# main.net
KiCad netlist of a schematic drawn in Altium Designer
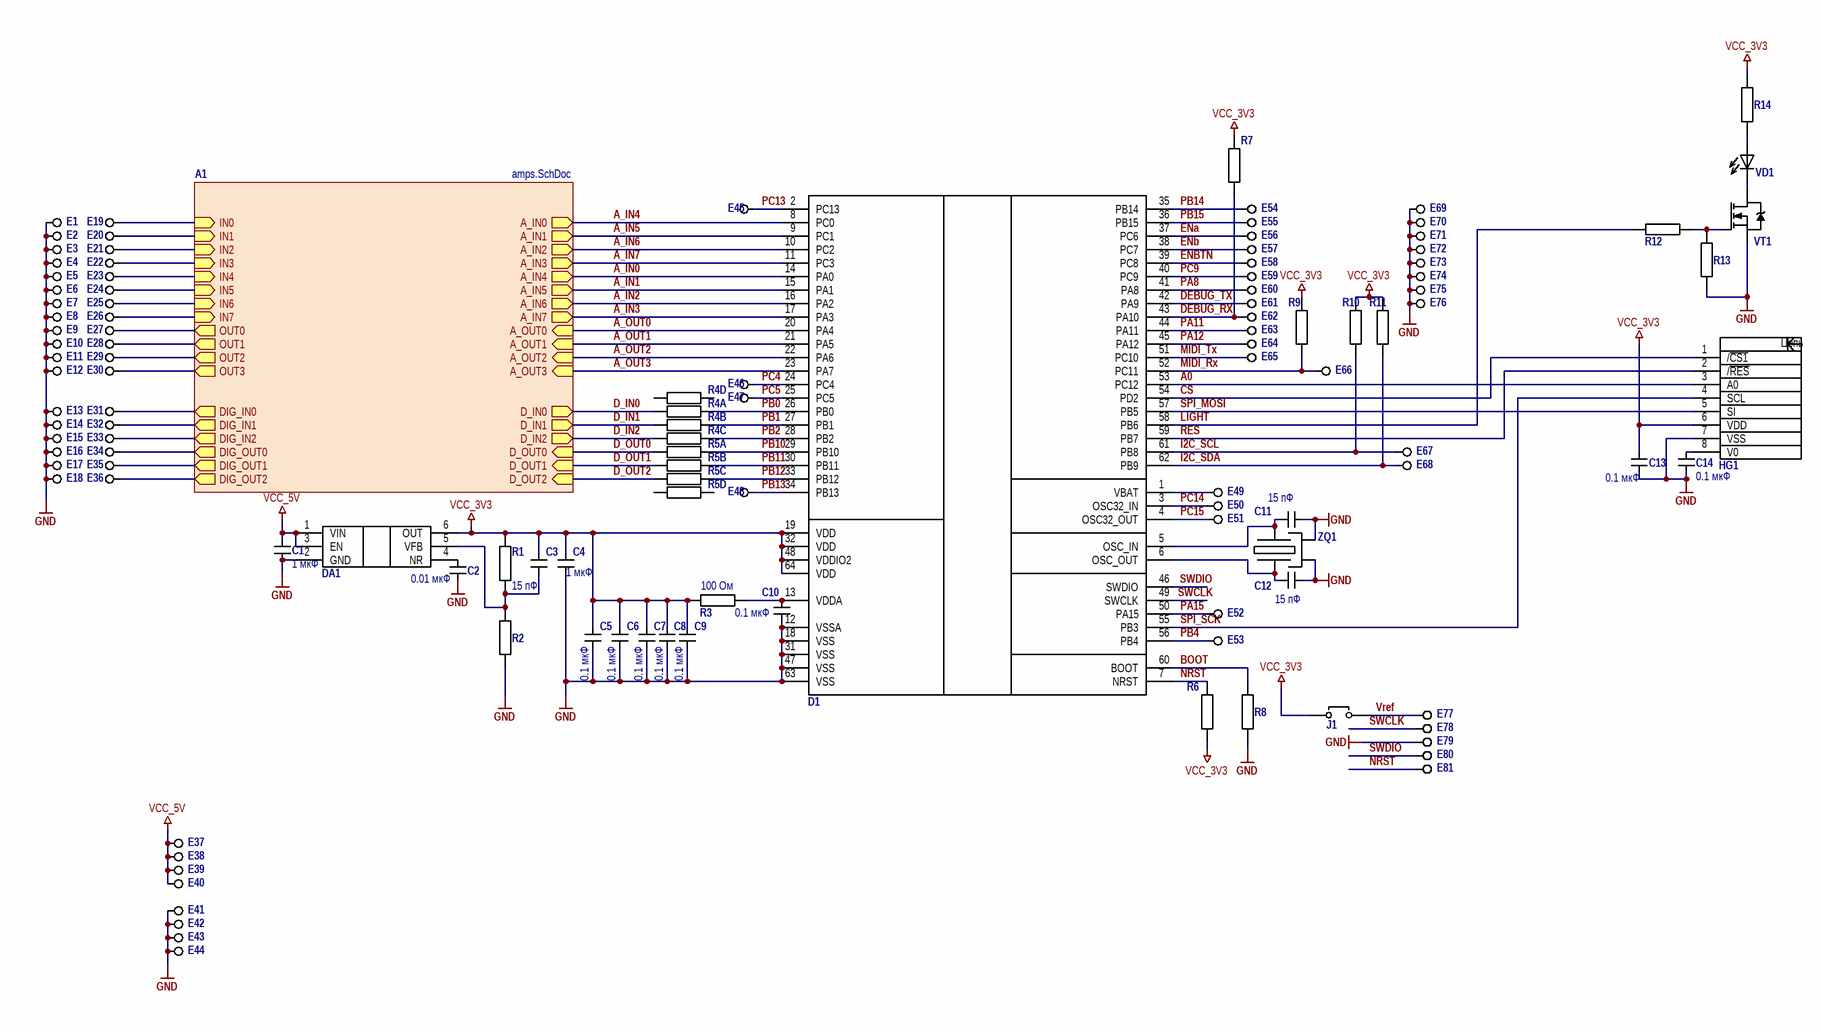
[diagram p0: main.SchDoc]

(export (version "E")
  (design (tool "Eeschema 10.0.6"))
  (components
    (comp (ref "C1")
      (value "1 мкФ")
      (footprint "CAPC1608X08L")
      (description "Чип 0603 16в 1мкФ")
      (fields (field (name "Comment") "C0603_16v_1u"))
      (libsource (lib "SKBEP LLC Server") (part "Cap_cer"))
    )
    (comp (ref "C2")
      (value "0.01 мкФ")
      (footprint "CAPC1608X08L")
      (description "Чип 0603 50в 0,01мкФ")
      (fields (field (name "Comment") "C0603_50v_0,01u"))
      (libsource (lib "SKBEP LLC Server") (part "Cap_cer"))
    )
    (comp (ref "C3")
      (value "15 пФ")
      (footprint "CAPC1608X08L")
      (description "Чип 0603 50в 15 пФ")
      (fields (field (name "Comment") "C0603_50v_15p"))
      (libsource (lib "SKBEP LLC Server") (part "Cap_cer"))
    )
    (comp (ref "C4")
      (value "1 мкФ")
      (footprint "CAPC1608X08L")
      (description "Чип 0603 16в 1мкФ")
      (fields (field (name "Comment") "C0603_16v_1u"))
      (libsource (lib "SKBEP LLC Server") (part "Cap_cer"))
    )
    (comp (ref "C5")
      (value "0.1 мкФ")
      (footprint "CAPC1608X08L")
      (description "Чип 0603 50в 0,1мкФ")
      (fields (field (name "Comment") "C0603_50v_0,1u"))
      (libsource (lib "SKBEP LLC Server") (part "Cap_cer"))
    )
    (comp (ref "C6")
      (value "0.1 мкФ")
      (footprint "CAPC1608X08L")
      (description "Чип 0603 50в 0,1мкФ")
      (fields (field (name "Comment") "C0603_50v_0,1u"))
      (libsource (lib "SKBEP LLC Server") (part "Cap_cer"))
    )
    (comp (ref "C7")
      (value "0.1 мкФ")
      (footprint "CAPC1608X08L")
      (description "Чип 0603 50в 0,1мкФ")
      (fields (field (name "Comment") "C0603_50v_0,1u"))
      (libsource (lib "SKBEP LLC Server") (part "Cap_cer"))
    )
    (comp (ref "C8")
      (value "0.1 мкФ")
      (footprint "CAPC1608X08L")
      (description "Чип 0603 50в 0,1мкФ")
      (fields (field (name "Comment") "C0603_50v_0,1u"))
      (libsource (lib "SKBEP LLC Server") (part "Cap_cer"))
    )
    (comp (ref "C9")
      (value "0.1 мкФ")
      (footprint "CAPC1608X08L")
      (description "Чип 0603 50в 0,1мкФ")
      (fields (field (name "Comment") "C0603_50v_0,1u"))
      (libsource (lib "SKBEP LLC Server") (part "Cap_cer"))
    )
    (comp (ref "C10")
      (value "0.1 мкФ")
      (footprint "CAPC1608X08L")
      (description "Чип 0603 50в 0,1мкФ")
      (fields (field (name "Comment") "C0603_50v_0,1u"))
      (libsource (lib "SKBEP LLC Server") (part "Cap_cer"))
    )
    (comp (ref "C11")
      (value "15 пФ")
      (footprint "CAPC1608X08L")
      (description "Чип 0603 50в 15 пФ")
      (fields (field (name "Comment") "C0603_50v_15p"))
      (libsource (lib "SKBEP LLC Server") (part "Cap_cer"))
    )
    (comp (ref "C12")
      (value "15 пФ")
      (footprint "CAPC1608X08L")
      (description "Чип 0603 50в 15 пФ")
      (fields (field (name "Comment") "C0603_50v_15p"))
      (libsource (lib "SKBEP LLC Server") (part "Cap_cer"))
    )
    (comp (ref "C13")
      (value "0.1 мкФ")
      (footprint "CAPC1608X08L")
      (description "Чип 0603 50в 0,1мкФ")
      (fields (field (name "Comment") "C0603_50v_0,1u"))
      (libsource (lib "SKBEP LLC Server") (part "Cap_cer"))
    )
    (comp (ref "C14")
      (value "0.1 мкФ")
      (footprint "CAPC1608X08L")
      (description "Чип 0603 50в 0,1мкФ")
      (fields (field (name "Comment") "C0603_50v_0,1u"))
      (libsource (lib "SKBEP LLC Server") (part "Cap_cer"))
    )
    (comp (ref "D1")
      (value "STM32F091RB6")
      (footprint "TSQFP50P_10x10_64N")
      (description "ARM®-based 32-bit MCU, up to 256 KB Flash")
      (libsource (lib "SKBEP LLC Server") (part "STM32F091RB6"))
    )
    (comp (ref "DA1")
      (value "TPS73001DBVT")
      (footprint "SOT95P280X145-6N")
      (description "TPS730 Low-Noise, High PSRR, RF, 200-mA Low-Dropout Linear Regulators")
      (libsource (lib "AltiumLib") (part "TPS73001"))
    )
    (comp (ref "E1")
      (value "CON 0.9mm")
      (footprint "con_0.9mm")
      (description "Контакт 0,9мм")
      (libsource (lib "SKBEP LLC Server") (part "pad"))
    )
    (comp (ref "E2")
      (value "CON 0.9mm")
      (footprint "con_0.9mm")
      (description "Контакт 0,9мм")
      (libsource (lib "SKBEP LLC Server") (part "pad"))
    )
    (comp (ref "E3")
      (value "CON 0.9mm")
      (footprint "con_0.9mm")
      (description "Контакт 0,9мм")
      (libsource (lib "SKBEP LLC Server") (part "pad"))
    )
    (comp (ref "E4")
      (value "CON 0.9mm")
      (footprint "con_0.9mm")
      (description "Контакт 0,9мм")
      (libsource (lib "SKBEP LLC Server") (part "pad"))
    )
    (comp (ref "E5")
      (value "CON 0.9mm")
      (footprint "con_0.9mm")
      (description "Контакт 0,9мм")
      (libsource (lib "SKBEP LLC Server") (part "pad"))
    )
    (comp (ref "E6")
      (value "CON 0.9mm")
      (footprint "con_0.9mm")
      (description "Контакт 0,9мм")
      (libsource (lib "SKBEP LLC Server") (part "pad"))
    )
    (comp (ref "E7")
      (value "CON 0.9mm")
      (footprint "con_0.9mm")
      (description "Контакт 0,9мм")
      (libsource (lib "SKBEP LLC Server") (part "pad"))
    )
    (comp (ref "E8")
      (value "CON 0.9mm")
      (footprint "con_0.9mm")
      (description "Контакт 0,9мм")
      (libsource (lib "SKBEP LLC Server") (part "pad"))
    )
    (comp (ref "E9")
      (value "CON 0.9mm")
      (footprint "con_0.9mm")
      (description "Контакт 0,9мм")
      (libsource (lib "SKBEP LLC Server") (part "pad"))
    )
    (comp (ref "E10")
      (value "CON 0.9mm")
      (footprint "con_0.9mm")
      (description "Контакт 0,9мм")
      (libsource (lib "SKBEP LLC Server") (part "pad"))
    )
    (comp (ref "E11")
      (value "CON 0.9mm")
      (footprint "con_0.9mm")
      (description "Контакт 0,9мм")
      (libsource (lib "SKBEP LLC Server") (part "pad"))
    )
    (comp (ref "E12")
      (value "CON 0.9mm")
      (footprint "con_0.9mm")
      (description "Контакт 0,9мм")
      (libsource (lib "SKBEP LLC Server") (part "pad"))
    )
    (comp (ref "E13")
      (value "CON 0.9mm")
      (footprint "con_0.9mm")
      (description "Контакт 0,9мм")
      (libsource (lib "SKBEP LLC Server") (part "pad"))
    )
    (comp (ref "E14")
      (value "CON 0.9mm")
      (footprint "con_0.9mm")
      (description "Контакт 0,9мм")
      (libsource (lib "SKBEP LLC Server") (part "pad"))
    )
    (comp (ref "E15")
      (value "CON 0.9mm")
      (footprint "con_0.9mm")
      (description "Контакт 0,9мм")
      (libsource (lib "SKBEP LLC Server") (part "pad"))
    )
    (comp (ref "E16")
      (value "CON 0.9mm")
      (footprint "con_0.9mm")
      (description "Контакт 0,9мм")
      (libsource (lib "SKBEP LLC Server") (part "pad"))
    )
    (comp (ref "E17")
      (value "CON 0.9mm")
      (footprint "con_0.9mm")
      (description "Контакт 0,9мм")
      (libsource (lib "SKBEP LLC Server") (part "pad"))
    )
    (comp (ref "E18")
      (value "CON 0.9mm")
      (footprint "con_0.9mm")
      (description "Контакт 0,9мм")
      (libsource (lib "SKBEP LLC Server") (part "pad"))
    )
    (comp (ref "E19")
      (value "CON 0.9mm")
      (footprint "con_0.9mm")
      (description "Контакт 0,9мм")
      (libsource (lib "SKBEP LLC Server") (part "pad"))
    )
    (comp (ref "E20")
      (value "CON 0.9mm")
      (footprint "con_0.9mm")
      (description "Контакт 0,9мм")
      (libsource (lib "SKBEP LLC Server") (part "pad"))
    )
    (comp (ref "E21")
      (value "CON 0.9mm")
      (footprint "con_0.9mm")
      (description "Контакт 0,9мм")
      (libsource (lib "SKBEP LLC Server") (part "pad"))
    )
    (comp (ref "E22")
      (value "CON 0.9mm")
      (footprint "con_0.9mm")
      (description "Контакт 0,9мм")
      (libsource (lib "SKBEP LLC Server") (part "pad"))
    )
    (comp (ref "E23")
      (value "CON 0.9mm")
      (footprint "con_0.9mm")
      (description "Контакт 0,9мм")
      (libsource (lib "SKBEP LLC Server") (part "pad"))
    )
    (comp (ref "E24")
      (value "CON 0.9mm")
      (footprint "con_0.9mm")
      (description "Контакт 0,9мм")
      (libsource (lib "SKBEP LLC Server") (part "pad"))
    )
    (comp (ref "E25")
      (value "CON 0.9mm")
      (footprint "con_0.9mm")
      (description "Контакт 0,9мм")
      (libsource (lib "SKBEP LLC Server") (part "pad"))
    )
    (comp (ref "E26")
      (value "CON 0.9mm")
      (footprint "con_0.9mm")
      (description "Контакт 0,9мм")
      (libsource (lib "SKBEP LLC Server") (part "pad"))
    )
    (comp (ref "E27")
      (value "CON 0.9mm")
      (footprint "con_0.9mm")
      (description "Контакт 0,9мм")
      (libsource (lib "SKBEP LLC Server") (part "pad"))
    )
    (comp (ref "E28")
      (value "CON 0.9mm")
      (footprint "con_0.9mm")
      (description "Контакт 0,9мм")
      (libsource (lib "SKBEP LLC Server") (part "pad"))
    )
    (comp (ref "E29")
      (value "CON 0.9mm")
      (footprint "con_0.9mm")
      (description "Контакт 0,9мм")
      (libsource (lib "SKBEP LLC Server") (part "pad"))
    )
    (comp (ref "E30")
      (value "CON 0.9mm")
      (footprint "con_0.9mm")
      (description "Контакт 0,9мм")
      (libsource (lib "SKBEP LLC Server") (part "pad"))
    )
    (comp (ref "E31")
      (value "CON 0.9mm")
      (footprint "con_0.9mm")
      (description "Контакт 0,9мм")
      (libsource (lib "SKBEP LLC Server") (part "pad"))
    )
    (comp (ref "E32")
      (value "CON 0.9mm")
      (footprint "con_0.9mm")
      (description "Контакт 0,9мм")
      (libsource (lib "SKBEP LLC Server") (part "pad"))
    )
    (comp (ref "E33")
      (value "CON 0.9mm")
      (footprint "con_0.9mm")
      (description "Контакт 0,9мм")
      (libsource (lib "SKBEP LLC Server") (part "pad"))
    )
    (comp (ref "E34")
      (value "CON 0.9mm")
      (footprint "con_0.9mm")
      (description "Контакт 0,9мм")
      (libsource (lib "SKBEP LLC Server") (part "pad"))
    )
    (comp (ref "E35")
      (value "CON 0.9mm")
      (footprint "con_0.9mm")
      (description "Контакт 0,9мм")
      (libsource (lib "SKBEP LLC Server") (part "pad"))
    )
    (comp (ref "E36")
      (value "CON 0.9mm")
      (footprint "con_0.9mm")
      (description "Контакт 0,9мм")
      (libsource (lib "SKBEP LLC Server") (part "pad"))
    )
    (comp (ref "E37")
      (value "CON 0.9mm")
      (footprint "con_0.9mm")
      (description "Контакт 0,9мм")
      (libsource (lib "SKBEP LLC Server") (part "pad"))
    )
    (comp (ref "E38")
      (value "CON 0.9mm")
      (footprint "con_0.9mm")
      (description "Контакт 0,9мм")
      (libsource (lib "SKBEP LLC Server") (part "pad"))
    )
    (comp (ref "E39")
      (value "CON 0.9mm")
      (footprint "con_0.9mm")
      (description "Контакт 0,9мм")
      (libsource (lib "SKBEP LLC Server") (part "pad"))
    )
    (comp (ref "E40")
      (value "CON 0.9mm")
      (footprint "con_0.9mm")
      (description "Контакт 0,9мм")
      (libsource (lib "SKBEP LLC Server") (part "pad"))
    )
    (comp (ref "E41")
      (value "CON 0.9mm")
      (footprint "con_0.9mm")
      (description "Контакт 0,9мм")
      (libsource (lib "SKBEP LLC Server") (part "pad"))
    )
    (comp (ref "E42")
      (value "CON 0.9mm")
      (footprint "con_0.9mm")
      (description "Контакт 0,9мм")
      (libsource (lib "SKBEP LLC Server") (part "pad"))
    )
    (comp (ref "E43")
      (value "CON 0.9mm")
      (footprint "con_0.9mm")
      (description "Контакт 0,9мм")
      (libsource (lib "SKBEP LLC Server") (part "pad"))
    )
    (comp (ref "E44")
      (value "CON 0.9mm")
      (footprint "con_0.9mm")
      (description "Контакт 0,9мм")
      (libsource (lib "SKBEP LLC Server") (part "pad"))
    )
    (comp (ref "E45")
      (value "CON 0.9mm")
      (footprint "con_0.9mm")
      (description "Контакт 0,9мм")
      (libsource (lib "SKBEP LLC Server") (part "pad"))
    )
    (comp (ref "E46")
      (value "CON 0.9mm")
      (footprint "con_0.9mm")
      (description "Контакт 0,9мм")
      (libsource (lib "SKBEP LLC Server") (part "pad"))
    )
    (comp (ref "E47")
      (value "CON 0.9mm")
      (footprint "con_0.9mm")
      (description "Контакт 0,9мм")
      (libsource (lib "SKBEP LLC Server") (part "pad"))
    )
    (comp (ref "E48")
      (value "CON 0.9mm")
      (footprint "con_0.9mm")
      (description "Контакт 0,9мм")
      (libsource (lib "SKBEP LLC Server") (part "pad"))
    )
    (comp (ref "E49")
      (value "CON 0.9mm")
      (footprint "con_0.9mm")
      (description "Контакт 0,9мм")
      (libsource (lib "SKBEP LLC Server") (part "pad"))
    )
    (comp (ref "E50")
      (value "CON 0.9mm")
      (footprint "con_0.9mm")
      (description "Контакт 0,9мм")
      (libsource (lib "SKBEP LLC Server") (part "pad"))
    )
    (comp (ref "E51")
      (value "CON 0.9mm")
      (footprint "con_0.9mm")
      (description "Контакт 0,9мм")
      (libsource (lib "SKBEP LLC Server") (part "pad"))
    )
    (comp (ref "E52")
      (value "CON 0.9mm")
      (footprint "con_0.9mm")
      (description "Контакт 0,9мм")
      (libsource (lib "SKBEP LLC Server") (part "pad"))
    )
    (comp (ref "E53")
      (value "CON 0.9mm")
      (footprint "con_0.9mm")
      (description "Контакт 0,9мм")
      (libsource (lib "SKBEP LLC Server") (part "pad"))
    )
    (comp (ref "E54")
      (value "CON 0.9mm")
      (footprint "con_0.9mm")
      (description "Контакт 0,9мм")
      (libsource (lib "SKBEP LLC Server") (part "pad"))
    )
    (comp (ref "E55")
      (value "CON 0.9mm")
      (footprint "con_0.9mm")
      (description "Контакт 0,9мм")
      (libsource (lib "SKBEP LLC Server") (part "pad"))
    )
    (comp (ref "E56")
      (value "CON 0.9mm")
      (footprint "con_0.9mm")
      (description "Контакт 0,9мм")
      (libsource (lib "SKBEP LLC Server") (part "pad"))
    )
    (comp (ref "E57")
      (value "CON 0.9mm")
      (footprint "con_0.9mm")
      (description "Контакт 0,9мм")
      (libsource (lib "SKBEP LLC Server") (part "pad"))
    )
    (comp (ref "E58")
      (value "CON 0.9mm")
      (footprint "con_0.9mm")
      (description "Контакт 0,9мм")
      (libsource (lib "SKBEP LLC Server") (part "pad"))
    )
    (comp (ref "E59")
      (value "CON 0.9mm")
      (footprint "con_0.9mm")
      (description "Контакт 0,9мм")
      (libsource (lib "SKBEP LLC Server") (part "pad"))
    )
    (comp (ref "E60")
      (value "CON 0.9mm")
      (footprint "con_0.9mm")
      (description "Контакт 0,9мм")
      (libsource (lib "SKBEP LLC Server") (part "pad"))
    )
    (comp (ref "E61")
      (value "CON 0.9mm")
      (footprint "con_0.9mm")
      (description "Контакт 0,9мм")
      (libsource (lib "SKBEP LLC Server") (part "pad"))
    )
    (comp (ref "E62")
      (value "CON 0.9mm")
      (footprint "con_0.9mm")
      (description "Контакт 0,9мм")
      (libsource (lib "SKBEP LLC Server") (part "pad"))
    )
    (comp (ref "E63")
      (value "CON 0.9mm")
      (footprint "con_0.9mm")
      (description "Контакт 0,9мм")
      (libsource (lib "SKBEP LLC Server") (part "pad"))
    )
    (comp (ref "E64")
      (value "CON 0.9mm")
      (footprint "con_0.9mm")
      (description "Контакт 0,9мм")
      (libsource (lib "SKBEP LLC Server") (part "pad"))
    )
    (comp (ref "E65")
      (value "CON 0.9mm")
      (footprint "con_0.9mm")
      (description "Контакт 0,9мм")
      (libsource (lib "SKBEP LLC Server") (part "pad"))
    )
    (comp (ref "E66")
      (value "CON 0.9mm")
      (footprint "con_0.9mm")
      (description "Контакт 0,9мм")
      (libsource (lib "SKBEP LLC Server") (part "pad"))
    )
    (comp (ref "E67")
      (value "CON 0.9mm")
      (footprint "con_0.9mm")
      (description "Контакт 0,9мм")
      (libsource (lib "SKBEP LLC Server") (part "pad"))
    )
    (comp (ref "E68")
      (value "CON 0.9mm")
      (footprint "con_0.9mm")
      (description "Контакт 0,9мм")
      (libsource (lib "SKBEP LLC Server") (part "pad"))
    )
    (comp (ref "E69")
      (value "CON 0.9mm")
      (footprint "con_0.9mm")
      (description "Контакт 0,9мм")
      (libsource (lib "SKBEP LLC Server") (part "pad"))
    )
    (comp (ref "E70")
      (value "CON 0.9mm")
      (footprint "con_0.9mm")
      (description "Контакт 0,9мм")
      (libsource (lib "SKBEP LLC Server") (part "pad"))
    )
    (comp (ref "E71")
      (value "CON 0.9mm")
      (footprint "con_0.9mm")
      (description "Контакт 0,9мм")
      (libsource (lib "SKBEP LLC Server") (part "pad"))
    )
    (comp (ref "E72")
      (value "CON 0.9mm")
      (footprint "con_0.9mm")
      (description "Контакт 0,9мм")
      (libsource (lib "SKBEP LLC Server") (part "pad"))
    )
    (comp (ref "E73")
      (value "CON 0.9mm")
      (footprint "con_0.9mm")
      (description "Контакт 0,9мм")
      (libsource (lib "SKBEP LLC Server") (part "pad"))
    )
    (comp (ref "E74")
      (value "CON 0.9mm")
      (footprint "con_0.9mm")
      (description "Контакт 0,9мм")
      (libsource (lib "SKBEP LLC Server") (part "pad"))
    )
    (comp (ref "E75")
      (value "CON 0.9mm")
      (footprint "con_0.9mm")
      (description "Контакт 0,9мм")
      (libsource (lib "SKBEP LLC Server") (part "pad"))
    )
    (comp (ref "E76")
      (value "CON 0.9mm")
      (footprint "con_0.9mm")
      (description "Контакт 0,9мм")
      (libsource (lib "SKBEP LLC Server") (part "pad"))
    )
    (comp (ref "E77")
      (value "CON 0.9mm")
      (footprint "con_0.9mm")
      (description "Контакт 0,9мм")
      (libsource (lib "SKBEP LLC Server") (part "pad"))
    )
    (comp (ref "E78")
      (value "CON 0.9mm")
      (footprint "con_0.9mm")
      (description "Контакт 0,9мм")
      (libsource (lib "SKBEP LLC Server") (part "pad"))
    )
    (comp (ref "E79")
      (value "CON 0.9mm")
      (footprint "con_0.9mm")
      (description "Контакт 0,9мм")
      (libsource (lib "SKBEP LLC Server") (part "pad"))
    )
    (comp (ref "E80")
      (value "CON 0.9mm")
      (footprint "con_0.9mm")
      (description "Контакт 0,9мм")
      (libsource (lib "SKBEP LLC Server") (part "pad"))
    )
    (comp (ref "E81")
      (value "CON 0.9mm")
      (footprint "con_0.9mm")
      (description "Контакт 0,9мм")
      (libsource (lib "SKBEP LLC Server") (part "pad"))
    )
    (comp (ref "HG1")
      (value "MT-12864")
      (footprint "MT-12864")
      (description "LCD индикатор MT-12864")
      (libsource (lib "SKBEP LLC Server") (part "MT-12864"))
    )
    (comp (ref "J1")
      (value "Jumper_1x1")
      (footprint "jumper 1x1")
      (description "Перемычка под пайку 1мм")
      (libsource (lib "SKBEP LLC Server") (part "jumper"))
    )
    (comp (ref "R1")
      (value "RES0603_51k")
      (footprint "RESC1608X04N")
      (description "Чип 0603 51 кОм")
      (libsource (lib "SKBEP LLC Server") (part "chip_res"))
    )
    (comp (ref "R2")
      (value "RES0603_30k±1%")
      (footprint "RESC1608X04N")
      (description "Чип 0603 30 кОм")
      (libsource (lib "SKBEP LLC Server") (part "chip_res"))
    )
    (comp (ref "R3")
      (value "100 Ом")
      (footprint "RESC1608X04N")
      (description "Чип 0603 100 Ом")
      (fields (field (name "Comment") "RES0603_100r"))
      (libsource (lib "SKBEP LLC Server") (part "chip_res"))
    )
    (comp (ref "R4")
      (value "CAT16-470J4")
      (footprint "CAC-80P320X160-8N")
      (description "Сборка 47 Ом")
      (libsource (lib "SKBEP LLC Server") (part "res_arr"))
    )
    (comp (ref "R5")
      (value "CAT16-470J4")
      (footprint "CAC-80P320X160-8N")
      (description "Сборка 47 Ом")
      (libsource (lib "SKBEP LLC Server") (part "res_arr"))
    )
    (comp (ref "R6")
      (value "RES0603_10k")
      (footprint "RESC1608X04N")
      (description "Чип 0603 10 кОм")
      (libsource (lib "SKBEP LLC Server") (part "chip_res"))
    )
    (comp (ref "R7")
      (value "RES0603_10k")
      (footprint "RESC1608X04N")
      (description "Чип 0603 10 кОм")
      (libsource (lib "SKBEP LLC Server") (part "chip_res"))
    )
    (comp (ref "R8")
      (value "RES0603_10k")
      (footprint "RESC1608X04N")
      (description "Чип 0603 10 кОм")
      (libsource (lib "SKBEP LLC Server") (part "chip_res"))
    )
    (comp (ref "R9")
      (value "RES0603_10k")
      (footprint "RESC1608X04N")
      (description "Чип 0603 10 кОм")
      (libsource (lib "SKBEP LLC Server") (part "chip_res"))
    )
    (comp (ref "R10")
      (value "RES0603_10k")
      (footprint "RESC1608X04N")
      (description "Чип 0603 10 кОм")
      (libsource (lib "SKBEP LLC Server") (part "chip_res"))
    )
    (comp (ref "R11")
      (value "RES0603_10k")
      (footprint "RESC1608X04N")
      (description "Чип 0603 10 кОм")
      (libsource (lib "SKBEP LLC Server") (part "chip_res"))
    )
    (comp (ref "R12")
      (value "RES0603_47R")
      (footprint "RESC1608X04N")
      (description "Чип 0603 47 Ом")
      (libsource (lib "SKBEP LLC Server") (part "chip_res"))
    )
    (comp (ref "R13")
      (value "RES0603_10k")
      (footprint "RESC1608X04N")
      (description "Чип 0603 10 кОм")
      (libsource (lib "SKBEP LLC Server") (part "chip_res"))
    )
    (comp (ref "R14")
      (value "RES0603_47R")
      (footprint "RESC1608X04N")
      (description "Чип 0603 47 Ом")
      (libsource (lib "SKBEP LLC Server") (part "chip_res"))
    )
    (comp (ref "VD1")
      (value "S11-161A-5W")
      (footprint "S11-161A-5W")
      (description "Светодиод зелёный 5mm")
      (libsource (lib "SKBEP LLC Server") (part "led"))
    )
    (comp (ref "VT1")
      (value "IRLML2402")
      (footprint "SOT95P245X110-3N")
      (description "sot-23 HEXFET MOSFET")
      (libsource (lib "SKBEP LLC Server") (part "N-single_sot23"))
    )
    (comp (ref "ZQ1")
      (value "TX3 12.0000 MHZ")
      (footprint "CDFN/DFN")
      (description "Кварцевый резонатор 12 МГц")
      (libsource (lib "SKBEP LLC Server") (part "Quartz_4pin"))
    )
  )
  (nets
    (net (code "1") (name "/A0") (class "Default")
      (node (ref "D1") (pin "53") (pinfunction "PC12_53") (pintype "passive"))
      (node (ref "HG1") (pin "3") (pinfunction "A0_3") (pintype "passive"))
    )
    (net (code "2") (name "/A_IN0") (class "Default")
      (node (ref "D1") (pin "14") (pinfunction "PA0_14") (pintype "passive"))
    )
    (net (code "3") (name "/A_IN1") (class "Default")
      (node (ref "D1") (pin "15") (pinfunction "PA1_15") (pintype "passive"))
    )
    (net (code "4") (name "/A_IN2") (class "Default")
      (node (ref "D1") (pin "16") (pinfunction "PA2_16") (pintype "passive"))
    )
    (net (code "5") (name "/A_IN3") (class "Default")
      (node (ref "D1") (pin "17") (pinfunction "PA3_17") (pintype "passive"))
    )
    (net (code "6") (name "/A_IN4") (class "Default")
      (node (ref "D1") (pin "8") (pinfunction "PC0_8") (pintype "passive"))
    )
    (net (code "7") (name "/A_IN5") (class "Default")
      (node (ref "D1") (pin "9") (pinfunction "PC1_9") (pintype "passive"))
    )
    (net (code "8") (name "/A_IN6") (class "Default")
      (node (ref "D1") (pin "10") (pinfunction "PC2_10") (pintype "passive"))
    )
    (net (code "9") (name "/A_IN7") (class "Default")
      (node (ref "D1") (pin "11") (pinfunction "PC3_11") (pintype "passive"))
    )
    (net (code "10") (name "/A_OUT0") (class "Default")
      (node (ref "D1") (pin "20") (pinfunction "PA4_20") (pintype "passive"))
    )
    (net (code "11") (name "/A_OUT1") (class "Default")
      (node (ref "D1") (pin "21") (pinfunction "PA5_21") (pintype "passive"))
    )
    (net (code "12") (name "/A_OUT2") (class "Default")
      (node (ref "D1") (pin "22") (pinfunction "PA6_22") (pintype "passive"))
    )
    (net (code "13") (name "/A_OUT3") (class "Default")
      (node (ref "D1") (pin "23") (pinfunction "PA7_23") (pintype "passive"))
    )
    (net (code "14") (name "/BOOT") (class "Default")
      (node (ref "D1") (pin "60") (pinfunction "BOOT_60") (pintype "passive"))
      (node (ref "R8") (pin "2") (pinfunction "2_2") (pintype "passive"))
    )
    (net (code "15") (name "/DEBUG_RX") (class "Default")
      (node (ref "D1") (pin "43") (pinfunction "PA10_43") (pintype "passive"))
      (node (ref "E62") (pin "1") (pinfunction "1_1") (pintype "passive"))
      (node (ref "R7") (pin "1") (pinfunction "1_1") (pintype "passive"))
    )
    (net (code "16") (name "/DEBUG_TX") (class "Default")
      (node (ref "D1") (pin "42") (pinfunction "PA9_42") (pintype "passive"))
      (node (ref "E61") (pin "1") (pinfunction "1_1") (pintype "passive"))
    )
    (net (code "17") (name "/DIG_IN0") (class "Default")
      (node (ref "E31") (pin "1") (pinfunction "1_1") (pintype "passive"))
    )
    (net (code "18") (name "/DIG_IN1") (class "Default")
      (node (ref "E32") (pin "1") (pinfunction "1_1") (pintype "passive"))
    )
    (net (code "19") (name "/DIG_IN2") (class "Default")
      (node (ref "E33") (pin "1") (pinfunction "1_1") (pintype "passive"))
    )
    (net (code "20") (name "/DIG_OUT0") (class "Default")
      (node (ref "E34") (pin "1") (pinfunction "1_1") (pintype "passive"))
    )
    (net (code "21") (name "/DIG_OUT1") (class "Default")
      (node (ref "E35") (pin "1") (pinfunction "1_1") (pintype "passive"))
    )
    (net (code "22") (name "/DIG_OUT2") (class "Default")
      (node (ref "E36") (pin "1") (pinfunction "1_1") (pintype "passive"))
    )
    (net (code "23") (name "/D_IN0") (class "Default")
      (node (ref "R4") (pin "1") (pinfunction "1_1") (pintype "passive"))
    )
    (net (code "24") (name "/D_IN1") (class "Default")
      (node (ref "R4") (pin "2") (pinfunction "2_2") (pintype "passive"))
    )
    (net (code "25") (name "/D_IN2") (class "Default")
      (node (ref "R4") (pin "3") (pinfunction "3_3") (pintype "passive"))
    )
    (net (code "26") (name "/D_OUT0") (class "Default")
      (node (ref "R5") (pin "1") (pinfunction "1_1") (pintype "passive"))
    )
    (net (code "27") (name "/D_OUT1") (class "Default")
      (node (ref "R5") (pin "2") (pinfunction "2_2") (pintype "passive"))
    )
    (net (code "28") (name "/D_OUT2") (class "Default")
      (node (ref "R5") (pin "3") (pinfunction "3_3") (pintype "passive"))
    )
    (net (code "29") (name "/ENBTN") (class "Default")
      (node (ref "D1") (pin "39") (pinfunction "PC8_39") (pintype "passive"))
      (node (ref "E58") (pin "1") (pinfunction "1_1") (pintype "passive"))
    )
    (net (code "30") (name "/ENa") (class "Default")
      (node (ref "D1") (pin "37") (pinfunction "PC6_37") (pintype "passive"))
      (node (ref "E56") (pin "1") (pinfunction "1_1") (pintype "passive"))
    )
    (net (code "31") (name "/ENb") (class "Default")
      (node (ref "D1") (pin "38") (pinfunction "PC7_38") (pintype "passive"))
      (node (ref "E57") (pin "1") (pinfunction "1_1") (pintype "passive"))
    )
    (net (code "32") (name "/I2C_SCL") (class "Default")
      (node (ref "D1") (pin "61") (pinfunction "PB8_61") (pintype "passive"))
      (node (ref "E67") (pin "1") (pinfunction "1_1") (pintype "passive"))
      (node (ref "R10") (pin "1") (pinfunction "1_1") (pintype "passive"))
    )
    (net (code "33") (name "/I2C_SDA") (class "Default")
      (node (ref "D1") (pin "62") (pinfunction "PB9_62") (pintype "passive"))
      (node (ref "E68") (pin "1") (pinfunction "1_1") (pintype "passive"))
      (node (ref "R11") (pin "1") (pinfunction "1_1") (pintype "passive"))
    )
    (net (code "34") (name "/IN0") (class "Default")
      (node (ref "E19") (pin "1") (pinfunction "1_1") (pintype "passive"))
    )
    (net (code "35") (name "/IN1") (class "Default")
      (node (ref "E20") (pin "1") (pinfunction "1_1") (pintype "passive"))
    )
    (net (code "36") (name "/IN2") (class "Default")
      (node (ref "E21") (pin "1") (pinfunction "1_1") (pintype "passive"))
    )
    (net (code "37") (name "/IN3") (class "Default")
      (node (ref "E22") (pin "1") (pinfunction "1_1") (pintype "passive"))
    )
    (net (code "38") (name "/IN4") (class "Default")
      (node (ref "E23") (pin "1") (pinfunction "1_1") (pintype "passive"))
    )
    (net (code "39") (name "/IN5") (class "Default")
      (node (ref "E24") (pin "1") (pinfunction "1_1") (pintype "passive"))
    )
    (net (code "40") (name "/IN6") (class "Default")
      (node (ref "E25") (pin "1") (pinfunction "1_1") (pintype "passive"))
    )
    (net (code "41") (name "/IN7") (class "Default")
      (node (ref "E26") (pin "1") (pinfunction "1_1") (pintype "passive"))
    )
    (net (code "42") (name "/LIGHT") (class "Default")
      (node (ref "D1") (pin "58") (pinfunction "PB6_58") (pintype "passive"))
      (node (ref "R12") (pin "2") (pinfunction "2_2") (pintype "passive"))
    )
    (net (code "43") (name "/MIDI_Rx") (class "Default")
      (node (ref "D1") (pin "52") (pinfunction "PC11_52") (pintype "passive"))
      (node (ref "E66") (pin "1") (pinfunction "1_1") (pintype "passive"))
      (node (ref "R9") (pin "1") (pinfunction "1_1") (pintype "passive"))
    )
    (net (code "44") (name "/MIDI_Tx") (class "Default")
      (node (ref "D1") (pin "51") (pinfunction "PC10_51") (pintype "passive"))
      (node (ref "E65") (pin "1") (pinfunction "1_1") (pintype "passive"))
    )
    (net (code "45") (name "/NRST") (class "Default")
      (node (ref "D1") (pin "7") (pinfunction "NRST_7") (pintype "passive"))
      (node (ref "E81") (pin "1") (pinfunction "1_1") (pintype "passive"))
      (node (ref "R6") (pin "2") (pinfunction "2_2") (pintype "passive"))
    )
    (net (code "46") (name "/OUT0") (class "Default")
      (node (ref "E27") (pin "1") (pinfunction "1_1") (pintype "passive"))
    )
    (net (code "47") (name "/OUT1") (class "Default")
      (node (ref "E28") (pin "1") (pinfunction "1_1") (pintype "passive"))
    )
    (net (code "48") (name "/OUT2") (class "Default")
      (node (ref "E29") (pin "1") (pinfunction "1_1") (pintype "passive"))
    )
    (net (code "49") (name "/OUT3") (class "Default")
      (node (ref "E30") (pin "1") (pinfunction "1_1") (pintype "passive"))
    )
    (net (code "50") (name "/PA8") (class "Default")
      (node (ref "D1") (pin "41") (pinfunction "PA8_41") (pintype "passive"))
      (node (ref "E60") (pin "1") (pinfunction "1_1") (pintype "passive"))
    )
    (net (code "51") (name "/PA11") (class "Default")
      (node (ref "D1") (pin "44") (pinfunction "PA11_44") (pintype "passive"))
      (node (ref "E63") (pin "1") (pinfunction "1_1") (pintype "passive"))
    )
    (net (code "52") (name "/PA12") (class "Default")
      (node (ref "D1") (pin "45") (pinfunction "PA12_45") (pintype "passive"))
      (node (ref "E64") (pin "1") (pinfunction "1_1") (pintype "passive"))
    )
    (net (code "53") (name "/PA15") (class "Default")
      (node (ref "D1") (pin "50") (pinfunction "PA15_50") (pintype "passive"))
      (node (ref "E52") (pin "1") (pinfunction "1_1") (pintype "passive"))
    )
    (net (code "54") (name "/PB0") (class "Default")
      (node (ref "D1") (pin "26") (pinfunction "PB0_26") (pintype "passive"))
      (node (ref "R4") (pin "8") (pinfunction "8_8") (pintype "passive"))
    )
    (net (code "55") (name "/PB1") (class "Default")
      (node (ref "D1") (pin "27") (pinfunction "PB1_27") (pintype "passive"))
      (node (ref "R4") (pin "7") (pinfunction "7_7") (pintype "passive"))
    )
    (net (code "56") (name "/PB2") (class "Default")
      (node (ref "D1") (pin "28") (pinfunction "PB2_28") (pintype "passive"))
      (node (ref "R4") (pin "6") (pinfunction "6_6") (pintype "passive"))
    )
    (net (code "57") (name "/PB4") (class "Default")
      (node (ref "D1") (pin "56") (pinfunction "PB4_56") (pintype "passive"))
      (node (ref "E53") (pin "1") (pinfunction "1_1") (pintype "passive"))
    )
    (net (code "58") (name "/PB10") (class "Default")
      (node (ref "D1") (pin "29") (pinfunction "PB10_29") (pintype "passive"))
      (node (ref "R5") (pin "8") (pinfunction "8_8") (pintype "passive"))
    )
    (net (code "59") (name "/PB11") (class "Default")
      (node (ref "D1") (pin "30") (pinfunction "PB11_30") (pintype "passive"))
      (node (ref "R5") (pin "7") (pinfunction "7_7") (pintype "passive"))
    )
    (net (code "60") (name "/PB12") (class "Default")
      (node (ref "D1") (pin "33") (pinfunction "PB12_33") (pintype "passive"))
      (node (ref "R5") (pin "6") (pinfunction "6_6") (pintype "passive"))
    )
    (net (code "61") (name "/PB13") (class "Default")
      (node (ref "D1") (pin "34") (pinfunction "PB13_34") (pintype "passive"))
      (node (ref "E48") (pin "1") (pinfunction "1_1") (pintype "passive"))
    )
    (net (code "62") (name "/PB14") (class "Default")
      (node (ref "D1") (pin "35") (pinfunction "PB14_35") (pintype "passive"))
      (node (ref "E54") (pin "1") (pinfunction "1_1") (pintype "passive"))
    )
    (net (code "63") (name "/PB15") (class "Default")
      (node (ref "D1") (pin "36") (pinfunction "PB15_36") (pintype "passive"))
      (node (ref "E55") (pin "1") (pinfunction "1_1") (pintype "passive"))
    )
    (net (code "64") (name "/PC9") (class "Default")
      (node (ref "D1") (pin "40") (pinfunction "PC9_40") (pintype "passive"))
      (node (ref "E59") (pin "1") (pinfunction "1_1") (pintype "passive"))
    )
    (net (code "65") (name "/PC13") (class "Default")
      (node (ref "D1") (pin "2") (pinfunction "PC13_2") (pintype "passive"))
      (node (ref "E45") (pin "1") (pinfunction "1_1") (pintype "passive"))
    )
    (net (code "66") (name "/PC14") (class "Default")
      (node (ref "D1") (pin "3") (pinfunction "OSC32_IN_3") (pintype "passive"))
      (node (ref "E50") (pin "1") (pinfunction "1_1") (pintype "passive"))
    )
    (net (code "67") (name "/PC15") (class "Default")
      (node (ref "D1") (pin "4") (pinfunction "OSC32_OUT_4") (pintype "passive"))
      (node (ref "E51") (pin "1") (pinfunction "1_1") (pintype "passive"))
    )
    (net (code "68") (name "/PС4") (class "Default")
      (node (ref "D1") (pin "24") (pinfunction "PC4_24") (pintype "passive"))
      (node (ref "E46") (pin "1") (pinfunction "1_1") (pintype "passive"))
    )
    (net (code "69") (name "/PС5") (class "Default")
      (node (ref "D1") (pin "25") (pinfunction "PC5_25") (pintype "passive"))
      (node (ref "E47") (pin "1") (pinfunction "1_1") (pintype "passive"))
    )
    (net (code "70") (name "/SPI_MOSI") (class "Default")
      (node (ref "D1") (pin "57") (pinfunction "PB5_57") (pintype "passive"))
      (node (ref "HG1") (pin "5") (pinfunction "SI_5") (pintype "passive"))
    )
    (net (code "71") (name "/SPI_SCK") (class "Default")
      (node (ref "D1") (pin "55") (pinfunction "PB3_55") (pintype "passive"))
      (node (ref "HG1") (pin "4") (pinfunction "SCL_4") (pintype "passive"))
    )
    (net (code "72") (name "/SWCLK") (class "Default")
      (node (ref "D1") (pin "49") (pinfunction "SWCLK_49") (pintype "passive"))
      (node (ref "E78") (pin "1") (pinfunction "1_1") (pintype "passive"))
    )
    (net (code "73") (name "/SWDIO") (class "Default")
      (node (ref "D1") (pin "46") (pinfunction "SWDIO_46") (pintype "passive"))
      (node (ref "E80") (pin "1") (pinfunction "1_1") (pintype "passive"))
    )
    (net (code "74") (name "/Vref") (class "Default")
      (node (ref "E77") (pin "1") (pinfunction "1_1") (pintype "passive"))
      (node (ref "J1") (pin "2") (pinfunction "2_2") (pintype "passive"))
    )
    (net (code "75") (name "/~{CS}") (class "Default")
      (node (ref "D1") (pin "54") (pinfunction "PD2_54") (pintype "passive"))
      (node (ref "HG1") (pin "1") (pinfunction "/~{CS1}_1") (pintype "passive"))
    )
    (net (code "76") (name "/~{RES}") (class "Default")
      (node (ref "D1") (pin "59") (pinfunction "PB7_59") (pintype "passive"))
      (node (ref "HG1") (pin "2") (pinfunction "/~{RES}_2") (pintype "passive"))
    )
    (net (code "77") (name "GND") (class "Default")
      (node (ref "C1") (pin "1") (pinfunction "1_1") (pintype "passive"))
      (node (ref "C10") (pin "1") (pinfunction "1_1") (pintype "passive"))
      (node (ref "C11") (pin "2") (pinfunction "2_2") (pintype "passive"))
      (node (ref "C12") (pin "2") (pinfunction "2_2") (pintype "passive"))
      (node (ref "C13") (pin "1") (pinfunction "1_1") (pintype "passive"))
      (node (ref "C14") (pin "1") (pinfunction "1_1") (pintype "passive"))
      (node (ref "C2") (pin "1") (pinfunction "1_1") (pintype "passive"))
      (node (ref "C4") (pin "1") (pinfunction "1_1") (pintype "passive"))
      (node (ref "C5") (pin "1") (pinfunction "1_1") (pintype "passive"))
      (node (ref "C6") (pin "1") (pinfunction "1_1") (pintype "passive"))
      (node (ref "C7") (pin "1") (pinfunction "1_1") (pintype "passive"))
      (node (ref "C8") (pin "1") (pinfunction "1_1") (pintype "passive"))
      (node (ref "C9") (pin "1") (pinfunction "1_1") (pintype "passive"))
      (node (ref "D1") (pin "12") (pinfunction "VSSA_12") (pintype "passive"))
      (node (ref "D1") (pin "18") (pinfunction "VSS_18") (pintype "passive"))
      (node (ref "D1") (pin "31") (pinfunction "VSS_31") (pintype "passive"))
      (node (ref "D1") (pin "47") (pinfunction "VSS_47") (pintype "passive"))
      (node (ref "D1") (pin "63") (pinfunction "VSS_63") (pintype "passive"))
      (node (ref "DA1") (pin "2") (pinfunction "GND_2") (pintype "passive"))
      (node (ref "E1") (pin "1") (pinfunction "1_1") (pintype "passive"))
      (node (ref "E10") (pin "1") (pinfunction "1_1") (pintype "passive"))
      (node (ref "E11") (pin "1") (pinfunction "1_1") (pintype "passive"))
      (node (ref "E12") (pin "1") (pinfunction "1_1") (pintype "passive"))
      (node (ref "E13") (pin "1") (pinfunction "1_1") (pintype "passive"))
      (node (ref "E14") (pin "1") (pinfunction "1_1") (pintype "passive"))
      (node (ref "E15") (pin "1") (pinfunction "1_1") (pintype "passive"))
      (node (ref "E16") (pin "1") (pinfunction "1_1") (pintype "passive"))
      (node (ref "E17") (pin "1") (pinfunction "1_1") (pintype "passive"))
      (node (ref "E18") (pin "1") (pinfunction "1_1") (pintype "passive"))
      (node (ref "E2") (pin "1") (pinfunction "1_1") (pintype "passive"))
      (node (ref "E3") (pin "1") (pinfunction "1_1") (pintype "passive"))
      (node (ref "E4") (pin "1") (pinfunction "1_1") (pintype "passive"))
      (node (ref "E41") (pin "1") (pinfunction "1_1") (pintype "passive"))
      (node (ref "E42") (pin "1") (pinfunction "1_1") (pintype "passive"))
      (node (ref "E43") (pin "1") (pinfunction "1_1") (pintype "passive"))
      (node (ref "E44") (pin "1") (pinfunction "1_1") (pintype "passive"))
      (node (ref "E5") (pin "1") (pinfunction "1_1") (pintype "passive"))
      (node (ref "E6") (pin "1") (pinfunction "1_1") (pintype "passive"))
      (node (ref "E69") (pin "1") (pinfunction "1_1") (pintype "passive"))
      (node (ref "E7") (pin "1") (pinfunction "1_1") (pintype "passive"))
      (node (ref "E70") (pin "1") (pinfunction "1_1") (pintype "passive"))
      (node (ref "E71") (pin "1") (pinfunction "1_1") (pintype "passive"))
      (node (ref "E72") (pin "1") (pinfunction "1_1") (pintype "passive"))
      (node (ref "E73") (pin "1") (pinfunction "1_1") (pintype "passive"))
      (node (ref "E74") (pin "1") (pinfunction "1_1") (pintype "passive"))
      (node (ref "E75") (pin "1") (pinfunction "1_1") (pintype "passive"))
      (node (ref "E76") (pin "1") (pinfunction "1_1") (pintype "passive"))
      (node (ref "E79") (pin "1") (pinfunction "1_1") (pintype "passive"))
      (node (ref "E8") (pin "1") (pinfunction "1_1") (pintype "passive"))
      (node (ref "E9") (pin "1") (pinfunction "1_1") (pintype "passive"))
      (node (ref "HG1") (pin "7") (pinfunction "VSS_7") (pintype "passive"))
      (node (ref "R13") (pin "1") (pinfunction "1_1") (pintype "passive"))
      (node (ref "R2") (pin "1") (pinfunction "1_1") (pintype "passive"))
      (node (ref "R8") (pin "1") (pinfunction "1_1") (pintype "passive"))
      (node (ref "VT1") (pin "2") (pinfunction "Source_2") (pintype "passive"))
      (node (ref "ZQ1") (pin "2") (pinfunction "2_2") (pintype "passive"))
      (node (ref "ZQ1") (pin "4") (pinfunction "4_4") (pintype "passive"))
    )
    (net (code "78") (name "Net-(D1-OSC_IN)") (class "Default")
      (node (ref "C11") (pin "1") (pinfunction "1_1") (pintype "passive"))
      (node (ref "D1") (pin "5") (pinfunction "OSC_IN_5") (pintype "passive"))
      (node (ref "ZQ1") (pin "3") (pinfunction "3_3") (pintype "passive"))
    )
    (net (code "79") (name "Net-(D1-OSC_OUT)") (class "Default")
      (node (ref "C12") (pin "1") (pinfunction "1_1") (pintype "passive"))
      (node (ref "D1") (pin "6") (pinfunction "OSC_OUT_6") (pintype "passive"))
      (node (ref "ZQ1") (pin "1") (pinfunction "1_1") (pintype "passive"))
    )
    (net (code "80") (name "Net-(D1-VBAT)") (class "Default")
      (node (ref "D1") (pin "1") (pinfunction "VBAT_1") (pintype "passive"))
      (node (ref "E49") (pin "1") (pinfunction "1_1") (pintype "passive"))
    )
    (net (code "81") (name "Net-(D1-VDDA)") (class "Default")
      (node (ref "C10") (pin "2") (pinfunction "2_2") (pintype "passive"))
      (node (ref "D1") (pin "13") (pinfunction "VDDA_13") (pintype "passive"))
      (node (ref "R3") (pin "2") (pinfunction "2_2") (pintype "passive"))
    )
    (net (code "82") (name "Net-(DA1-NR)") (class "Default")
      (node (ref "C2") (pin "2") (pinfunction "2_2") (pintype "passive"))
      (node (ref "DA1") (pin "4") (pinfunction "NR_4") (pintype "passive"))
    )
    (net (code "83") (name "Net-(DA1-VFB)") (class "Default")
      (node (ref "C3") (pin "1") (pinfunction "1_1") (pintype "passive"))
      (node (ref "DA1") (pin "5") (pinfunction "VFB_5") (pintype "passive"))
      (node (ref "R1") (pin "1") (pinfunction "1_1") (pintype "passive"))
      (node (ref "R2") (pin "2") (pinfunction "2_2") (pintype "passive"))
    )
    (net (code "84") (name "Net-(HG1-V0)") (class "Default")
      (node (ref "C14") (pin "2") (pinfunction "2_2") (pintype "passive"))
      (node (ref "HG1") (pin "8") (pinfunction "V0_8") (pintype "passive"))
    )
    (net (code "85") (name "Net-(VD1-A)") (class "Default")
      (node (ref "R14") (pin "1") (pinfunction "1_1") (pintype "passive"))
      (node (ref "VD1") (pin "2") (pinfunction "A_2") (pintype "passive"))
    )
    (net (code "86") (name "Net-(VD1-K)") (class "Default")
      (node (ref "VD1") (pin "1") (pinfunction "K_1") (pintype "passive"))
      (node (ref "VT1") (pin "3") (pinfunction "Drain_3") (pintype "passive"))
    )
    (net (code "87") (name "Net-(VT1-Gate)") (class "Default")
      (node (ref "R12") (pin "1") (pinfunction "1_1") (pintype "passive"))
      (node (ref "R13") (pin "2") (pinfunction "2_2") (pintype "passive"))
      (node (ref "VT1") (pin "1") (pinfunction "Gate_1") (pintype "passive"))
    )
    (net (code "88") (name "VCC_3V3") (class "Default")
      (node (ref "C13") (pin "2") (pinfunction "2_2") (pintype "passive"))
      (node (ref "C3") (pin "2") (pinfunction "2_2") (pintype "passive"))
      (node (ref "C4") (pin "2") (pinfunction "2_2") (pintype "passive"))
      (node (ref "C5") (pin "2") (pinfunction "2_2") (pintype "passive"))
      (node (ref "C6") (pin "2") (pinfunction "2_2") (pintype "passive"))
      (node (ref "C7") (pin "2") (pinfunction "2_2") (pintype "passive"))
      (node (ref "C8") (pin "2") (pinfunction "2_2") (pintype "passive"))
      (node (ref "C9") (pin "2") (pinfunction "2_2") (pintype "passive"))
      (node (ref "D1") (pin "19") (pinfunction "VDD_19") (pintype "passive"))
      (node (ref "D1") (pin "32") (pinfunction "VDD_32") (pintype "passive"))
      (node (ref "D1") (pin "48") (pinfunction "VDDIO2_48") (pintype "passive"))
      (node (ref "D1") (pin "64") (pinfunction "VDD_64") (pintype "passive"))
      (node (ref "DA1") (pin "6") (pinfunction "OUT_6") (pintype "passive"))
      (node (ref "HG1") (pin "6") (pinfunction "VDD_6") (pintype "passive"))
      (node (ref "J1") (pin "1") (pinfunction "1_1") (pintype "passive"))
      (node (ref "R1") (pin "2") (pinfunction "2_2") (pintype "passive"))
      (node (ref "R10") (pin "2") (pinfunction "2_2") (pintype "passive"))
      (node (ref "R11") (pin "2") (pinfunction "2_2") (pintype "passive"))
      (node (ref "R14") (pin "2") (pinfunction "2_2") (pintype "passive"))
      (node (ref "R3") (pin "1") (pinfunction "1_1") (pintype "passive"))
      (node (ref "R6") (pin "1") (pinfunction "1_1") (pintype "passive"))
      (node (ref "R7") (pin "2") (pinfunction "2_2") (pintype "passive"))
      (node (ref "R9") (pin "2") (pinfunction "2_2") (pintype "passive"))
    )
    (net (code "89") (name "VCC_5V") (class "Default")
      (node (ref "C1") (pin "2") (pinfunction "2_2") (pintype "passive"))
      (node (ref "DA1") (pin "1") (pinfunction "VIN_1") (pintype "passive"))
      (node (ref "DA1") (pin "3") (pinfunction "EN_3") (pintype "passive"))
      (node (ref "E37") (pin "1") (pinfunction "1_1") (pintype "passive"))
      (node (ref "E38") (pin "1") (pinfunction "1_1") (pintype "passive"))
      (node (ref "E39") (pin "1") (pinfunction "1_1") (pintype "passive"))
      (node (ref "E40") (pin "1") (pinfunction "1_1") (pintype "passive"))
    )
    (net (code "90") (name "unconnected-(R4-Pad4)") (class "Default")
      (node (ref "R4") (pin "4") (pinfunction "4_4") (pintype "passive"))
    )
    (net (code "91") (name "unconnected-(R4-Pad5)") (class "Default")
      (node (ref "R4") (pin "5") (pinfunction "5_5") (pintype "passive"))
    )
    (net (code "92") (name "unconnected-(R5-Pad4)") (class "Default")
      (node (ref "R5") (pin "4") (pinfunction "4_4") (pintype "passive"))
    )
    (net (code "93") (name "unconnected-(R5-Pad5)") (class "Default")
      (node (ref "R5") (pin "5") (pinfunction "5_5") (pintype "passive"))
    )
  )
)
